# Oscillator_32_768KHz.net
KiCad netlist of a schematic drawn in Altium Designer
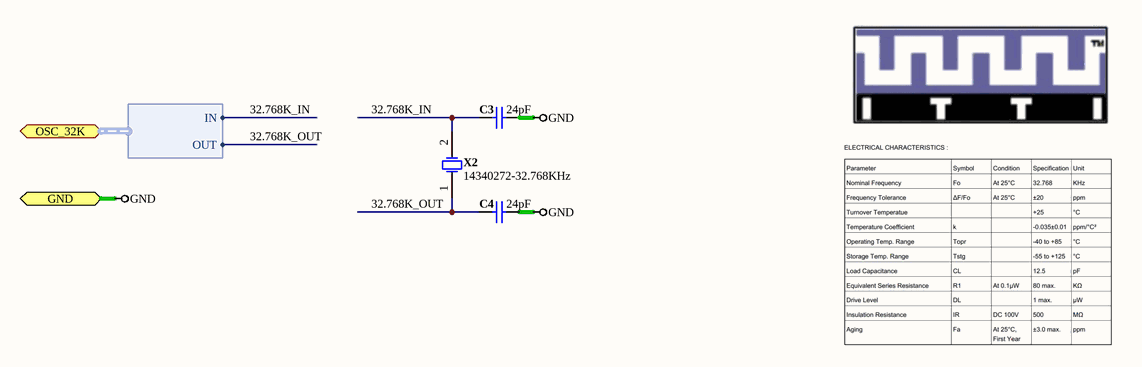
[diagram p0: Oscillator_32_768KHz.SchDoc]

(export (version "E")
  (design (tool "Eeschema 10.0.6"))
  (components
    (comp (ref "C3")
      (value "24pF")
      (footprint "CAPC0402(1005)60_N")
      (description "CAP 24pF 10V ±0.25pF 0402 (1005 Metric) Thickness 0.6mm SMD")
      (fields (field (name "TOLERANCE") "±0.25pF") (field (name "Comment") "CAP 24pF 10V 0402(1005)"))
      (libsource (lib "Altium Content Vault") (part "CMP-1034-00923-1"))
    )
    (comp (ref "C4")
      (value "24pF")
      (footprint "CAPC0402(1005)60_N")
      (description "CAP 24pF 10V ±0.25pF 0402 (1005 Metric) Thickness 0.6mm SMD")
      (fields (field (name "TOLERANCE") "±0.25pF") (field (name "Comment") "CAP 24pF 10V 0402(1005)"))
      (libsource (lib "Altium Content Vault") (part "CMP-1034-00923-1"))
    )
    (comp (ref "X2")
      (value "14340272-32.768KHz")
      (footprint "ITTI-14340272-32.768KHz-2_V")
      (description "Crystal, 32.768 KHz, -40 to 85 degC, 3.2 x 1.5 x 0.9 mm SMD")
      (fields (field (name "MANUFACTURER") "ITTI"))
      (libsource (lib "Altium Content Vault") (part "ITTI-14340272-2"))
    )
  )
  (nets
    (net (code "2") (name "/32.768K_IN") (class "Default")
      (node (ref "C3") (pin "2") (pinfunction "2_2") (pintype "passive"))
      (node (ref "X2") (pin "2") (pinfunction "X2_2") (pintype "passive"))
    )
    (net (code "3") (name "/32.768K_OUT") (class "Default")
      (node (ref "C4") (pin "2") (pinfunction "2_2") (pintype "passive"))
      (node (ref "X2") (pin "1") (pinfunction "X1_1") (pintype "passive"))
    )
    (net (code "5") (name "GND") (class "Default")
      (node (ref "C3") (pin "1") (pinfunction "1_1") (pintype "passive"))
      (node (ref "C4") (pin "1") (pinfunction "1_1") (pintype "passive"))
    )
  )
)
